# Scooter_-_Primary_Board_-_Schematic.net
KiCad netlist of a schematic drawn in Altium Designer
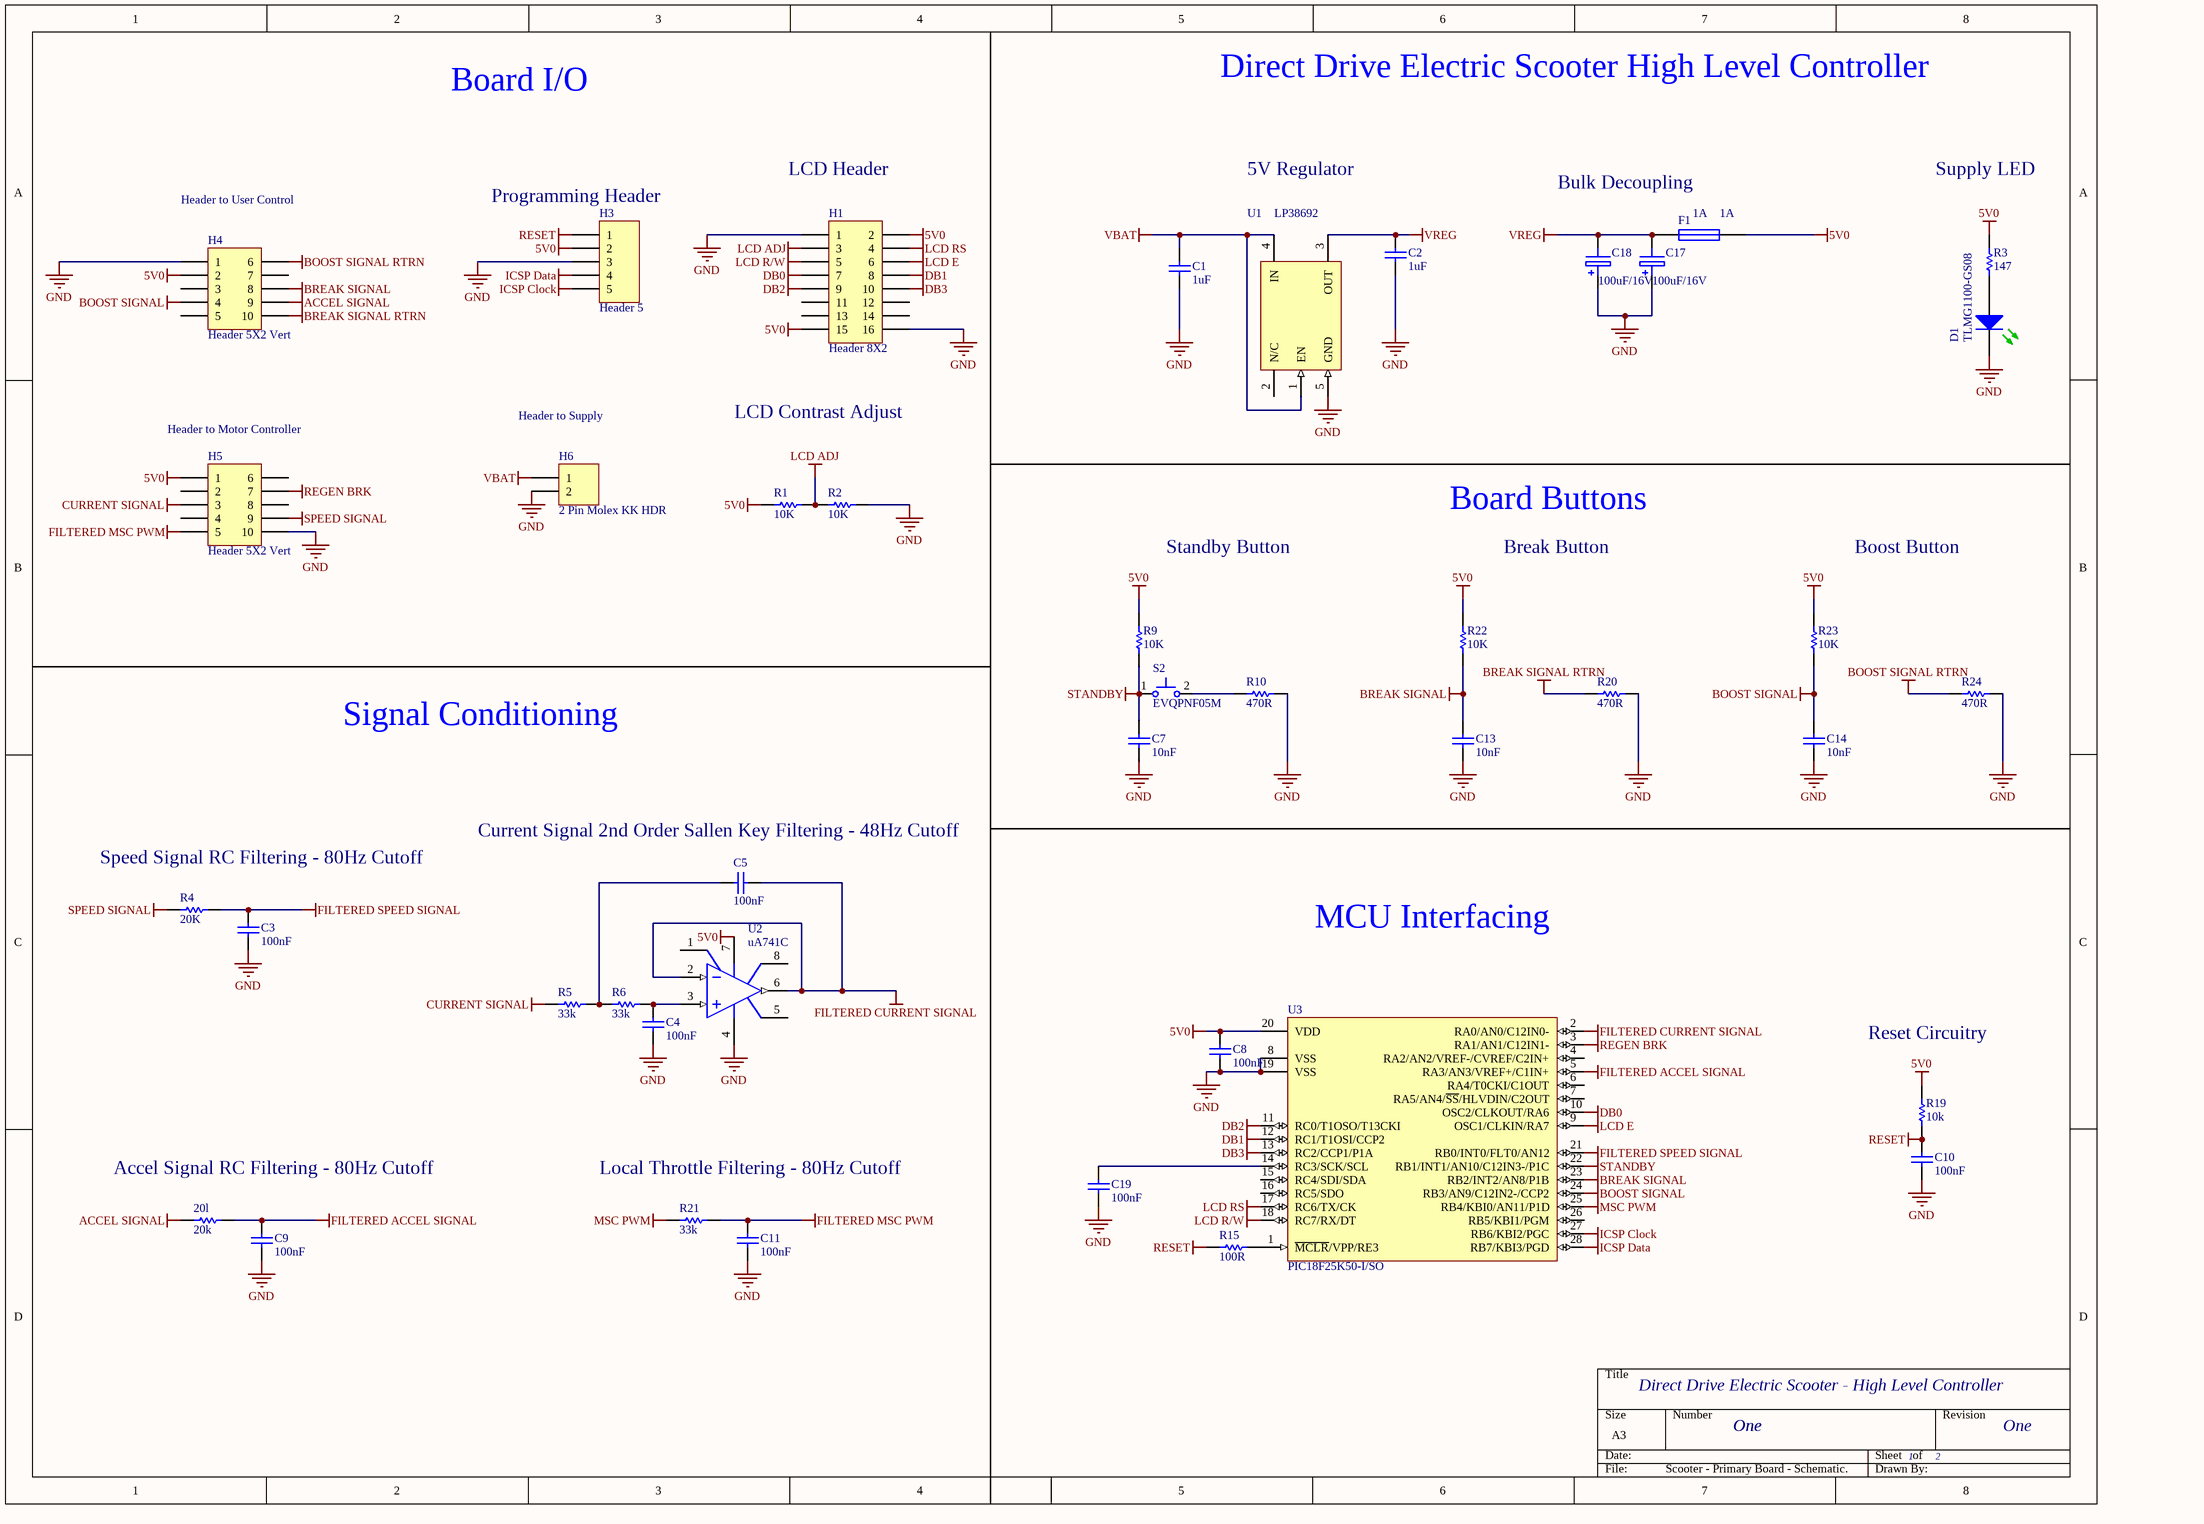
[diagram p0: Scooter - Primary Board - Schematic.SchDoc]

(export (version "E")
  (design (tool "Eeschema 10.0.6"))
  (components
    (comp (ref "20l")
      (value "20k")
      (footprint "RESC1608L")
      (description "RES 10.0K OHM 1/10W 5% 0603 SMD")
      (libsource (lib "ECE Components-Ver2") (part "RS_10K"))
    )
    (comp (ref "C1")
      (value "1uF")
      (footprint "CAPC1608L")
      (description "CAP CER 1uF Y5V -20% +80% 16V 0603")
      (libsource (lib "ECE Components-Ver2") (part "CC_1uF_0603"))
    )
    (comp (ref "C2")
      (value "1uF")
      (footprint "CAPC1608L")
      (description "CAP CER 1uF Y5V -20% +80% 16V 0603")
      (libsource (lib "ECE Components-Ver2") (part "CC_1uF_0603"))
    )
    (comp (ref "C3")
      (value "100nF")
      (footprint "CAPC1608L")
      (description "CAP CER 100nF X7R +-10% 50V 0603")
      (libsource (lib "ECE Components-Ver2") (part "CC_100nF_0603"))
    )
    (comp (ref "C4")
      (value "100nF")
      (footprint "CAPC1608L")
      (description "CAP CER 100nF X7R +-10% 50V 0603")
      (libsource (lib "ECE Components-Ver2") (part "CC_100nF_0603"))
    )
    (comp (ref "C5")
      (value "100nF")
      (footprint "CAPC1608L")
      (description "CAP CER 100nF X7R +-10% 50V 0603")
      (libsource (lib "ECE Components-Ver2") (part "CC_100nF_0603"))
    )
    (comp (ref "C7")
      (value "10nF")
      (footprint "CAPC1608L")
      (description "CAP CER 10nF X7R +-10% 50V 0603")
      (libsource (lib "ECE Components-Ver2") (part "CC_10nF_0603"))
    )
    (comp (ref "C8")
      (value "100nF")
      (footprint "CAPC1608L")
      (description "CAP CER 100nF X7R +-10% 50V 0603")
      (libsource (lib "ECE Components-Ver2") (part "CC_100nF_0603"))
    )
    (comp (ref "C9")
      (value "100nF")
      (footprint "CAPC1608L")
      (description "CAP CER 100nF X7R +-10% 50V 0603")
      (libsource (lib "ECE Components-Ver2") (part "CC_100nF_0603"))
    )
    (comp (ref "C10")
      (value "100nF")
      (footprint "CAPC1608L")
      (description "CAP CER 100nF X7R +-10% 50V 0603")
      (libsource (lib "ECE Components-Ver2") (part "CC_100nF_0603"))
    )
    (comp (ref "C11")
      (value "100nF")
      (footprint "CAPC1608L")
      (description "CAP CER 220nF Y5V -20% +80% 16V 0603")
      (libsource (lib "ECE Components-Ver2") (part "CC_220nF_0603"))
    )
    (comp (ref "C13")
      (value "10nF")
      (footprint "CAPC1608L")
      (description "CAP CER 10nF X7R +-10% 50V 0603")
      (libsource (lib "ECE Components-Ver2") (part "CC_10nF_0603"))
    )
    (comp (ref "C14")
      (value "10nF")
      (footprint "CAPC1608L")
      (description "CAP CER 10nF X7R +-10% 50V 0603")
      (libsource (lib "ECE Components-Ver2") (part "CC_10nF_0603"))
    )
    (comp (ref "C17")
      (value "100uF/16V")
      (footprint "NICH-1")
      (description "Nichcon WX series  SMT Aluminium Electrolytic Cap")
      (fields (field (name "MANUFACTURER") "Nichcon"))
      (libsource (lib "ECE Components-Ver2") (part "CA_100uF_16V_SMD"))
    )
    (comp (ref "C18")
      (value "100uF/16V")
      (footprint "NICH-1")
      (description "Nichcon WX series  SMT Aluminium Electrolytic Cap")
      (fields (field (name "MANUFACTURER") "Nichcon"))
      (libsource (lib "ECE Components-Ver2") (part "CA_100uF_16V_SMD"))
    )
    (comp (ref "C19")
      (value "100nF")
      (footprint "CAPC1608L")
      (description "CAP CER 100nF X7R +-10% 50V 0603")
      (libsource (lib "ECE Components-Ver2") (part "CC_100nF_0603"))
    )
    (comp (ref "D1")
      (value "TLMG1100-GS08")
      (footprint "LED0.8X1.6")
      (description "LED Green 0603")
      (fields
        (field (name "MANUFACTURER") "Vishay Semiconductor Opto Division")
        (field (name "MANUFACTURER PART NUMBER") "TLMG1100-GS08")
      )
      (libsource (lib "ECE Components-Ver2") (part "DL_TLMG1100"))
    )
    (comp (ref "F1")
      (value "1A")
      (footprint "RESC3216N")
      (description "Fuse 1.0A Very Fast Acting 1206")
      (fields (field (name "MANUFACTURER") "Multicomp") (field (name "ALTIUM_VALUE") "1A"))
      (libsource (lib "ECE Components-Ver2") (part "FS_Fuse_1.0A_SMD_1206"))
    )
    (comp (ref "H1")
      (value "Header 8X2")
      (footprint "HDR2X8")
      (description "Header, 8-Pin, Dual row")
      (fields (field (name "PUBLISHER") "Altium Limited"))
      (libsource (lib "Miscellaneous Connectors") (part "Header 8X2"))
    )
    (comp (ref "H3")
      (value "Header 5")
      (footprint "HDR1X5")
      (description "Header, 5-Pin")
      (fields (field (name "PUBLISHER") "Altium Limited"))
      (libsource (lib "Miscellaneous Connectors") (part "Header 5"))
    )
    (comp (ref "H4")
      (value "Header 5X2 Vert")
      (footprint "IDC2.54-V10D")
      (description "IDC Header, 2,54mm, 10-Pin, Vert")
      (libsource (lib "ECE Components_Ver4") (part "JA_HDR_IDC_5X2_VERT"))
    )
    (comp (ref "H5")
      (value "Header 5X2 Vert")
      (footprint "IDC2.54-V10D")
      (description "IDC Header, 2,54mm, 10-Pin, Vert")
      (libsource (lib "ECE Components_Ver4") (part "JA_HDR_IDC_5X2_VERT"))
    )
    (comp (ref "H6")
      (value "2 Pin Molex KK HDR")
      (footprint "MOLEX_KK_2_HDR")
      (description "CONN HEADER 2POS 2.54mm VERT_Thru Hole")
      (libsource (lib "ECE Components_Ver4") (part "JA_MOLEX_KK_2POS"))
    )
    (comp (ref "R1")
      (value "10K")
      (footprint "RESC1608L")
      (description "RES 10.0K OHM 1/10W 5% 0603 SMD")
      (libsource (lib "ECE Components-Ver2") (part "RS_10K"))
    )
    (comp (ref "R2")
      (value "10K")
      (footprint "RESC1608L")
      (description "RES 10.0K OHM 1/10W 5% 0603 SMD")
      (libsource (lib "ECE Components-Ver2") (part "RS_10K"))
    )
    (comp (ref "R3")
      (value "147")
      (footprint "RESC1608L")
      (description "RES 10.0K OHM 1/10W 5% 0603 SMD")
      (libsource (lib "ECE Components-Ver2") (part "RS_10K"))
    )
    (comp (ref "R4")
      (value "20K")
      (footprint "RESC1608L")
      (description "RES 10.0K OHM 1/10W 5% 0603 SMD")
      (libsource (lib "ECE Components-Ver2") (part "RS_10K"))
    )
    (comp (ref "R5")
      (value "33k")
      (footprint "RESC1608L")
      (description "RES 10.0K OHM 1/10W 5% 0603 SMD")
      (libsource (lib "ECE Components-Ver2") (part "RS_10K"))
    )
    (comp (ref "R6")
      (value "33k")
      (footprint "RESC1608L")
      (description "RES 10.0K OHM 1/10W 5% 0603 SMD")
      (libsource (lib "ECE Components-Ver2") (part "RS_10K"))
    )
    (comp (ref "R9")
      (value "10K")
      (footprint "RESC1608L")
      (description "RES 10.0K OHM 1/10W 5% 0603 SMD")
      (libsource (lib "ECE Components-Ver2") (part "RS_10K"))
    )
    (comp (ref "R10")
      (value "470R")
      (footprint "RESC1608L")
      (description "RES 470 OHM 1/10W 5% 0603 SMD")
      (libsource (lib "ECE Components-Ver2") (part "RS_470R"))
    )
    (comp (ref "R15")
      (value "100R")
      (footprint "RESC1608L")
      (description "RES 470 OHM 1/10W 5% 0603 SMD")
      (libsource (lib "ECE Components-Ver2") (part "RS_470R"))
    )
    (comp (ref "R19")
      (value "10k")
      (footprint "RESC1608L")
      (description "RES 470 OHM 1/10W 5% 0603 SMD")
      (libsource (lib "ECE Components-Ver2") (part "RS_470R"))
    )
    (comp (ref "R20")
      (value "470R")
      (footprint "RESC1608L")
      (description "RES 470 OHM 1/10W 5% 0603 SMD")
      (libsource (lib "ECE Components-Ver2") (part "RS_470R"))
    )
    (comp (ref "R21")
      (value "33k")
      (footprint "RESC1608L")
      (description "RES 10.0K OHM 1/10W 5% 0603 SMD")
      (libsource (lib "ECE Components-Ver2") (part "RS_10K"))
    )
    (comp (ref "R22")
      (value "10K")
      (footprint "RESC1608L")
      (description "RES 10.0K OHM 1/10W 5% 0603 SMD")
      (libsource (lib "ECE Components-Ver2") (part "RS_10K"))
    )
    (comp (ref "R23")
      (value "10K")
      (footprint "RESC1608L")
      (description "RES 10.0K OHM 1/10W 5% 0603 SMD")
      (libsource (lib "ECE Components-Ver2") (part "RS_10K"))
    )
    (comp (ref "R24")
      (value "470R")
      (footprint "RESC1608L")
      (description "RES 470 OHM 1/10W 5% 0603 SMD")
      (libsource (lib "ECE Components-Ver2") (part "RS_470R"))
    )
    (comp (ref "S2")
      (value "EVQPNF05M")
      (footprint "EVQPNF05M")
      (description "Panasonic 6 x 3.5mm SMD Light Touch Switch Type")
      (fields (field (name "MANUFACTURER") "Panasonic"))
      (libsource (lib "ECE Components-Ver2") (part "WS_EVQPNF05M"))
    )
    (comp (ref "U1")
      (value "LP38692")
      (footprint "SOT223-5N")
      (description "1000 mA, Low Voltage, Low Quiescent Current LDO Regulator, 5-Pin TO-220, Extended Temperature")
      (fields (field (name "PUBLISHER") "Altium Limited"))
      (libsource (lib "Microchip Power Mgt Line Regulator") (part "MCP1826-ADJE/AT"))
    )
    (comp (ref "U2")
      (value "uA741C")
      (footprint "SO8_N")
      (description "High Performance Operational Amplifier")
      (fields (field (name "PUBLISHER") "Altium Limited"))
      (libsource (lib "TI Operational Amplifier") (part "LM101AJG"))
    )
    (comp (ref "U3")
      (value "PIC18F25K50-I/SO")
      (footprint "SOIC-SO28_N")
      (fields (field (name "PUBLISHER") "Altium Limited"))
      (libsource (lib "Microchip Microcontroller 8-Bit PIC18") (part "PIC18F25K20T-I/SO"))
    )
  )
  (nets
    (net (code "1") (name "5V0") (class "Default")
      (node (ref "C8") (pin "2") (pinfunction "2_2") (pintype "passive"))
      (node (ref "F1") (pin "2") (pinfunction "2_2") (pintype "passive"))
      (node (ref "H1") (pin "15") (pinfunction "15_15") (pintype "passive"))
      (node (ref "H1") (pin "2") (pinfunction "2_2") (pintype "passive"))
      (node (ref "H3") (pin "2") (pinfunction "2_2") (pintype "passive"))
      (node (ref "H4") (pin "2") (pinfunction "2_2") (pintype "passive"))
      (node (ref "H5") (pin "1") (pinfunction "1_1") (pintype "passive"))
      (node (ref "R1") (pin "2") (pinfunction "2_2") (pintype "passive"))
      (node (ref "R19") (pin "2") (pinfunction "2_2") (pintype "passive"))
      (node (ref "R22") (pin "2") (pinfunction "2_2") (pintype "passive"))
      (node (ref "R23") (pin "2") (pinfunction "2_2") (pintype "passive"))
      (node (ref "R3") (pin "2") (pinfunction "2_2") (pintype "passive"))
      (node (ref "R9") (pin "2") (pinfunction "2_2") (pintype "passive"))
      (node (ref "U2") (pin "7") (pinfunction "V+_7") (pintype "power_in"))
      (node (ref "U3") (pin "20") (pinfunction "VDD_20") (pintype "power_in"))
    )
    (net (code "2") (name "ACCEL SIGNAL") (class "Default")
      (node (ref "20l") (pin "2") (pinfunction "2_2") (pintype "passive"))
      (node (ref "H4") (pin "9") (pinfunction "9_9") (pintype "passive"))
    )
    (net (code "3") (name "BOOST SIGNAL") (class "Default")
      (node (ref "C14") (pin "2") (pinfunction "2_2") (pintype "passive"))
      (node (ref "H4") (pin "4") (pinfunction "4_4") (pintype "passive"))
      (node (ref "R23") (pin "1") (pinfunction "1_1") (pintype "passive"))
      (node (ref "U3") (pin "24") (pinfunction "RB3/AN9/C12IN2-/CCP2_24") (pintype "bidirectional"))
    )
    (net (code "4") (name "BOOST SIGNAL RTRN") (class "Default")
      (node (ref "H4") (pin "6") (pinfunction "6_6") (pintype "passive"))
      (node (ref "R24") (pin "1") (pinfunction "1_1") (pintype "passive"))
    )
    (net (code "5") (name "BREAK SIGNAL") (class "Default")
      (node (ref "C13") (pin "1") (pinfunction "1_1") (pintype "passive"))
      (node (ref "H4") (pin "8") (pinfunction "8_8") (pintype "passive"))
      (node (ref "R22") (pin "1") (pinfunction "1_1") (pintype "passive"))
      (node (ref "U3") (pin "23") (pinfunction "RB2/INT2/AN8/P1B_23") (pintype "bidirectional"))
    )
    (net (code "6") (name "BREAK SIGNAL RTRN") (class "Default")
      (node (ref "H4") (pin "10") (pinfunction "10_10") (pintype "passive"))
      (node (ref "R20") (pin "1") (pinfunction "1_1") (pintype "passive"))
    )
    (net (code "7") (name "CURRENT SIGNAL") (class "Default")
      (node (ref "H5") (pin "3") (pinfunction "3_3") (pintype "passive"))
      (node (ref "R5") (pin "2") (pinfunction "2_2") (pintype "passive"))
    )
    (net (code "8") (name "DB0") (class "Default")
      (node (ref "H1") (pin "7") (pinfunction "7_7") (pintype "passive"))
      (node (ref "U3") (pin "10") (pinfunction "OSC2/CLKOUT/RA6_10") (pintype "bidirectional"))
    )
    (net (code "9") (name "DB1") (class "Default")
      (node (ref "H1") (pin "8") (pinfunction "8_8") (pintype "passive"))
      (node (ref "U3") (pin "12") (pinfunction "RC1/T1OSI/CCP2_12") (pintype "bidirectional"))
    )
    (net (code "10") (name "DB2") (class "Default")
      (node (ref "H1") (pin "9") (pinfunction "9_9") (pintype "passive"))
      (node (ref "U3") (pin "11") (pinfunction "RC0/T1OSO/T13CKI_11") (pintype "bidirectional"))
    )
    (net (code "11") (name "DB3") (class "Default")
      (node (ref "H1") (pin "10") (pinfunction "10_10") (pintype "passive"))
      (node (ref "U3") (pin "13") (pinfunction "RC2/CCP1/P1A_13") (pintype "bidirectional"))
    )
    (net (code "12") (name "FILTERED ACCEL SIGNAL") (class "Default")
      (node (ref "20l") (pin "1") (pinfunction "1_1") (pintype "passive"))
      (node (ref "C9") (pin "2") (pinfunction "2_2") (pintype "passive"))
      (node (ref "U3") (pin "5") (pinfunction "RA3/AN3/VREF+/C1IN+_5") (pintype "bidirectional"))
    )
    (net (code "13") (name "FILTERED CURRENT SIGNAL") (class "Default")
      (node (ref "C5") (pin "1") (pinfunction "1_1") (pintype "passive"))
      (node (ref "U2") (pin "2") (pinfunction "IN-_2") (pintype "input"))
      (node (ref "U2") (pin "6") (pinfunction "OUT_6") (pintype "output"))
      (node (ref "U3") (pin "2") (pinfunction "RA0/AN0/C12IN0-_2") (pintype "bidirectional"))
    )
    (net (code "14") (name "FILTERED MSC PWM") (class "Default")
      (node (ref "C11") (pin "2") (pinfunction "2_2") (pintype "passive"))
      (node (ref "H5") (pin "5") (pinfunction "5_5") (pintype "passive"))
      (node (ref "R21") (pin "1") (pinfunction "1_1") (pintype "passive"))
    )
    (net (code "15") (name "FILTERED SPEED SIGNAL") (class "Default")
      (node (ref "C3") (pin "2") (pinfunction "2_2") (pintype "passive"))
      (node (ref "R4") (pin "1") (pinfunction "1_1") (pintype "passive"))
      (node (ref "U3") (pin "21") (pinfunction "RB0/INT0/FLT0/AN12_21") (pintype "bidirectional"))
    )
    (net (code "16") (name "GND") (class "Default")
      (node (ref "C1") (pin "1") (pinfunction "1_1") (pintype "passive"))
      (node (ref "C10") (pin "1") (pinfunction "1_1") (pintype "passive"))
      (node (ref "C11") (pin "1") (pinfunction "1_1") (pintype "passive"))
      (node (ref "C13") (pin "2") (pinfunction "2_2") (pintype "passive"))
      (node (ref "C14") (pin "1") (pinfunction "1_1") (pintype "passive"))
      (node (ref "C17") (pin "2") (pintype "passive"))
      (node (ref "C18") (pin "2") (pintype "passive"))
      (node (ref "C19") (pin "1") (pinfunction "1_1") (pintype "passive"))
      (node (ref "C2") (pin "1") (pinfunction "1_1") (pintype "passive"))
      (node (ref "C3") (pin "1") (pinfunction "1_1") (pintype "passive"))
      (node (ref "C4") (pin "1") (pinfunction "1_1") (pintype "passive"))
      (node (ref "C7") (pin "1") (pinfunction "1_1") (pintype "passive"))
      (node (ref "C8") (pin "1") (pinfunction "1_1") (pintype "passive"))
      (node (ref "C9") (pin "1") (pinfunction "1_1") (pintype "passive"))
      (node (ref "D1") (pin "2") (pinfunction "K_2") (pintype "passive"))
      (node (ref "H1") (pin "1") (pinfunction "1_1") (pintype "passive"))
      (node (ref "H1") (pin "16") (pinfunction "16_16") (pintype "passive"))
      (node (ref "H3") (pin "3") (pinfunction "3_3") (pintype "passive"))
      (node (ref "H4") (pin "1") (pinfunction "1_1") (pintype "passive"))
      (node (ref "H5") (pin "10") (pinfunction "10_10") (pintype "passive"))
      (node (ref "H6") (pin "2") (pinfunction "2_2") (pintype "passive"))
      (node (ref "R10") (pin "2") (pinfunction "2_2") (pintype "passive"))
      (node (ref "R2") (pin "1") (pinfunction "1_1") (pintype "passive"))
      (node (ref "R20") (pin "2") (pinfunction "2_2") (pintype "passive"))
      (node (ref "R24") (pin "2") (pinfunction "2_2") (pintype "passive"))
      (node (ref "U1") (pin "5") (pinfunction "GND_5") (pintype "input"))
      (node (ref "U2") (pin "4") (pinfunction "V-_4") (pintype "power_in"))
      (node (ref "U3") (pin "19") (pinfunction "VSS_19") (pintype "power_in"))
      (node (ref "U3") (pin "8") (pinfunction "VSS_8") (pintype "power_in"))
    )
    (net (code "17") (name "ICSP Clock") (class "Default")
      (node (ref "H3") (pin "5") (pinfunction "5_5") (pintype "passive"))
      (node (ref "U3") (pin "27") (pinfunction "RB6/KBI2/PGC_27") (pintype "bidirectional"))
    )
    (net (code "18") (name "ICSP Data") (class "Default")
      (node (ref "H3") (pin "4") (pinfunction "4_4") (pintype "passive"))
      (node (ref "U3") (pin "28") (pinfunction "RB7/KBI3/PGD_28") (pintype "bidirectional"))
    )
    (net (code "19") (name "LCD ADJ") (class "Default")
      (node (ref "H1") (pin "3") (pinfunction "3_3") (pintype "passive"))
      (node (ref "R1") (pin "1") (pinfunction "1_1") (pintype "passive"))
      (node (ref "R2") (pin "2") (pinfunction "2_2") (pintype "passive"))
    )
    (net (code "20") (name "LCD E") (class "Default")
      (node (ref "H1") (pin "6") (pinfunction "6_6") (pintype "passive"))
      (node (ref "U3") (pin "9") (pinfunction "OSC1/CLKIN/RA7_9") (pintype "bidirectional"))
    )
    (net (code "21") (name "LCD RS") (class "Default")
      (node (ref "H1") (pin "4") (pinfunction "4_4") (pintype "passive"))
      (node (ref "U3") (pin "17") (pinfunction "RC6/TX/CK_17") (pintype "bidirectional"))
    )
    (net (code "22") (name "LCD R{slash}W") (class "Default")
      (node (ref "H1") (pin "5") (pinfunction "5_5") (pintype "passive"))
      (node (ref "U3") (pin "18") (pinfunction "RC7/RX/DT_18") (pintype "bidirectional"))
    )
    (net (code "23") (name "MSC PWM") (class "Default")
      (node (ref "R21") (pin "2") (pinfunction "2_2") (pintype "passive"))
      (node (ref "U3") (pin "25") (pinfunction "RB4/KBI0/AN11/P1D_25") (pintype "bidirectional"))
    )
    (net (code "24") (name "Net-(C5-Pad2)") (class "Default")
      (node (ref "C5") (pin "2") (pinfunction "2_2") (pintype "passive"))
      (node (ref "R5") (pin "1") (pinfunction "1_1") (pintype "passive"))
      (node (ref "R6") (pin "2") (pinfunction "2_2") (pintype "passive"))
    )
    (net (code "25") (name "Net-(D1-A)") (class "Default")
      (node (ref "D1") (pin "1") (pinfunction "A_1") (pintype "passive"))
      (node (ref "R3") (pin "1") (pinfunction "1_1") (pintype "passive"))
    )
    (net (code "26") (name "Net-(R10-Pad1)") (class "Default")
      (node (ref "R10") (pin "1") (pinfunction "1_1") (pintype "passive"))
      (node (ref "S2") (pin "2") (pinfunction "2_2") (pintype "passive"))
    )
    (net (code "27") (name "Net-(U2-IN+)") (class "Default")
      (node (ref "C4") (pin "2") (pinfunction "2_2") (pintype "passive"))
      (node (ref "R6") (pin "1") (pinfunction "1_1") (pintype "passive"))
      (node (ref "U2") (pin "3") (pinfunction "IN+_3") (pintype "input"))
    )
    (net (code "28") (name "Net-(U3-RC3{slash}SCK{slash}SCL)") (class "Default")
      (node (ref "C19") (pin "2") (pinfunction "2_2") (pintype "passive"))
      (node (ref "U3") (pin "14") (pinfunction "RC3/SCK/SCL_14") (pintype "bidirectional"))
    )
    (net (code "29") (name "Net-(U3-~{MCLR}{slash}VPP{slash}RE3)") (class "Default")
      (node (ref "R15") (pin "2") (pinfunction "2_2") (pintype "passive"))
      (node (ref "U3") (pin "1") (pinfunction "~{MCLR}/VPP/RE3_1") (pintype "input"))
    )
    (net (code "30") (name "REGEN BRK") (class "Default")
      (node (ref "H5") (pin "7") (pinfunction "7_7") (pintype "passive"))
      (node (ref "U3") (pin "3") (pinfunction "RA1/AN1/C12IN1-_3") (pintype "bidirectional"))
    )
    (net (code "31") (name "RESET") (class "Default")
      (node (ref "C10") (pin "2") (pinfunction "2_2") (pintype "passive"))
      (node (ref "H3") (pin "1") (pinfunction "1_1") (pintype "passive"))
      (node (ref "R15") (pin "1") (pinfunction "1_1") (pintype "passive"))
      (node (ref "R19") (pin "1") (pinfunction "1_1") (pintype "passive"))
    )
    (net (code "32") (name "SPEED SIGNAL") (class "Default")
      (node (ref "H5") (pin "9") (pinfunction "9_9") (pintype "passive"))
      (node (ref "R4") (pin "2") (pinfunction "2_2") (pintype "passive"))
    )
    (net (code "33") (name "STANDBY") (class "Default")
      (node (ref "C7") (pin "2") (pinfunction "2_2") (pintype "passive"))
      (node (ref "R9") (pin "1") (pinfunction "1_1") (pintype "passive"))
      (node (ref "S2") (pin "1") (pinfunction "1_1") (pintype "passive"))
      (node (ref "U3") (pin "22") (pinfunction "RB1/INT1/AN10/C12IN3-/P1C_22") (pintype "bidirectional"))
    )
    (net (code "34") (name "VBAT") (class "Default")
      (node (ref "C1") (pin "2") (pinfunction "2_2") (pintype "passive"))
      (node (ref "H6") (pin "1") (pinfunction "1_1") (pintype "passive"))
      (node (ref "U1") (pin "1") (pinfunction "EN_1") (pintype "input"))
      (node (ref "U1") (pin "4") (pinfunction "IN_4") (pintype "power_in"))
    )
    (net (code "35") (name "VREG") (class "Default")
      (node (ref "C17") (pin "1") (pintype "passive"))
      (node (ref "C18") (pin "1") (pintype "passive"))
      (node (ref "C2") (pin "2") (pinfunction "2_2") (pintype "passive"))
      (node (ref "F1") (pin "1") (pinfunction "1_1") (pintype "passive"))
      (node (ref "U1") (pin "3") (pinfunction "OUT_3") (pintype "power_in"))
    )
    (net (code "36") (name "unconnected-(H1-Pad11)") (class "Default")
      (node (ref "H1") (pin "11") (pinfunction "11_11") (pintype "passive"))
    )
    (net (code "37") (name "unconnected-(H1-Pad12)") (class "Default")
      (node (ref "H1") (pin "12") (pinfunction "12_12") (pintype "passive"))
    )
    (net (code "38") (name "unconnected-(H1-Pad13)") (class "Default")
      (node (ref "H1") (pin "13") (pinfunction "13_13") (pintype "passive"))
    )
    (net (code "39") (name "unconnected-(H1-Pad14)") (class "Default")
      (node (ref "H1") (pin "14") (pinfunction "14_14") (pintype "passive"))
    )
    (net (code "40") (name "unconnected-(H4-Pad3)") (class "Default")
      (node (ref "H4") (pin "3") (pinfunction "3_3") (pintype "passive"))
    )
    (net (code "41") (name "unconnected-(H4-Pad5)") (class "Default")
      (node (ref "H4") (pin "5") (pinfunction "5_5") (pintype "passive"))
    )
    (net (code "42") (name "unconnected-(H4-Pad7)") (class "Default")
      (node (ref "H4") (pin "7") (pinfunction "7_7") (pintype "passive"))
    )
    (net (code "43") (name "unconnected-(H5-Pad2)") (class "Default")
      (node (ref "H5") (pin "2") (pinfunction "2_2") (pintype "passive"))
    )
    (net (code "44") (name "unconnected-(H5-Pad4)") (class "Default")
      (node (ref "H5") (pin "4") (pinfunction "4_4") (pintype "passive"))
    )
    (net (code "45") (name "unconnected-(H5-Pad6)") (class "Default")
      (node (ref "H5") (pin "6") (pinfunction "6_6") (pintype "passive"))
    )
    (net (code "46") (name "unconnected-(H5-Pad8)") (class "Default")
      (node (ref "H5") (pin "8") (pinfunction "8_8") (pintype "passive"))
    )
    (net (code "47") (name "unconnected-(U1-N{slash}C-Pad2)") (class "Default")
      (node (ref "U1") (pin "2") (pinfunction "N/C_2") (pintype "power_in"))
    )
    (net (code "48") (name "unconnected-(U2-BAL1{slash}CMPEN-Pad1)") (class "Default")
      (node (ref "U2") (pin "1") (pinfunction "BAL1/CMPEN_1") (pintype "passive"))
    )
    (net (code "49") (name "unconnected-(U2-BAL2-Pad5)") (class "Default")
      (node (ref "U2") (pin "5") (pinfunction "BAL2_5") (pintype "passive"))
    )
    (net (code "50") (name "unconnected-(U2-CMPEN-Pad8)") (class "Default")
      (node (ref "U2") (pin "8") (pinfunction "CMPEN_8") (pintype "passive"))
    )
    (net (code "51") (name "unconnected-(U3-RA2{slash}AN2{slash}VREF-{slash}CVREF{slash}C2IN+-Pad4)") (class "Default")
      (node (ref "U3") (pin "4") (pinfunction "RA2/AN2/VREF-/CVREF/C2IN+_4") (pintype "bidirectional"))
    )
    (net (code "52") (name "unconnected-(U3-RA4{slash}T0CKI{slash}C1OUT-Pad6)") (class "Default")
      (node (ref "U3") (pin "6") (pinfunction "RA4/T0CKI/C1OUT_6") (pintype "bidirectional"))
    )
    (net (code "53") (name "unconnected-(U3-RA5{slash}AN4{slash}~{SS}{slash}HLVDIN{slash}C2OUT-Pad7)") (class "Default")
      (node (ref "U3") (pin "7") (pinfunction "RA5/AN4/~{SS}/HLVDIN/C2OUT_7") (pintype "bidirectional"))
    )
    (net (code "54") (name "unconnected-(U3-RB5{slash}KBI1{slash}PGM-Pad26)") (class "Default")
      (node (ref "U3") (pin "26") (pinfunction "RB5/KBI1/PGM_26") (pintype "bidirectional"))
    )
    (net (code "55") (name "unconnected-(U3-RC4{slash}SDI{slash}SDA-Pad15)") (class "Default")
      (node (ref "U3") (pin "15") (pinfunction "RC4/SDI/SDA_15") (pintype "bidirectional"))
    )
    (net (code "56") (name "unconnected-(U3-RC5{slash}SDO-Pad16)") (class "Default")
      (node (ref "U3") (pin "16") (pinfunction "RC5/SDO_16") (pintype "bidirectional"))
    )
  )
)
